# utilidong-ftdi-uart-mk-1_0.net
KiCad netlist of a schematic drawn in EAGLE
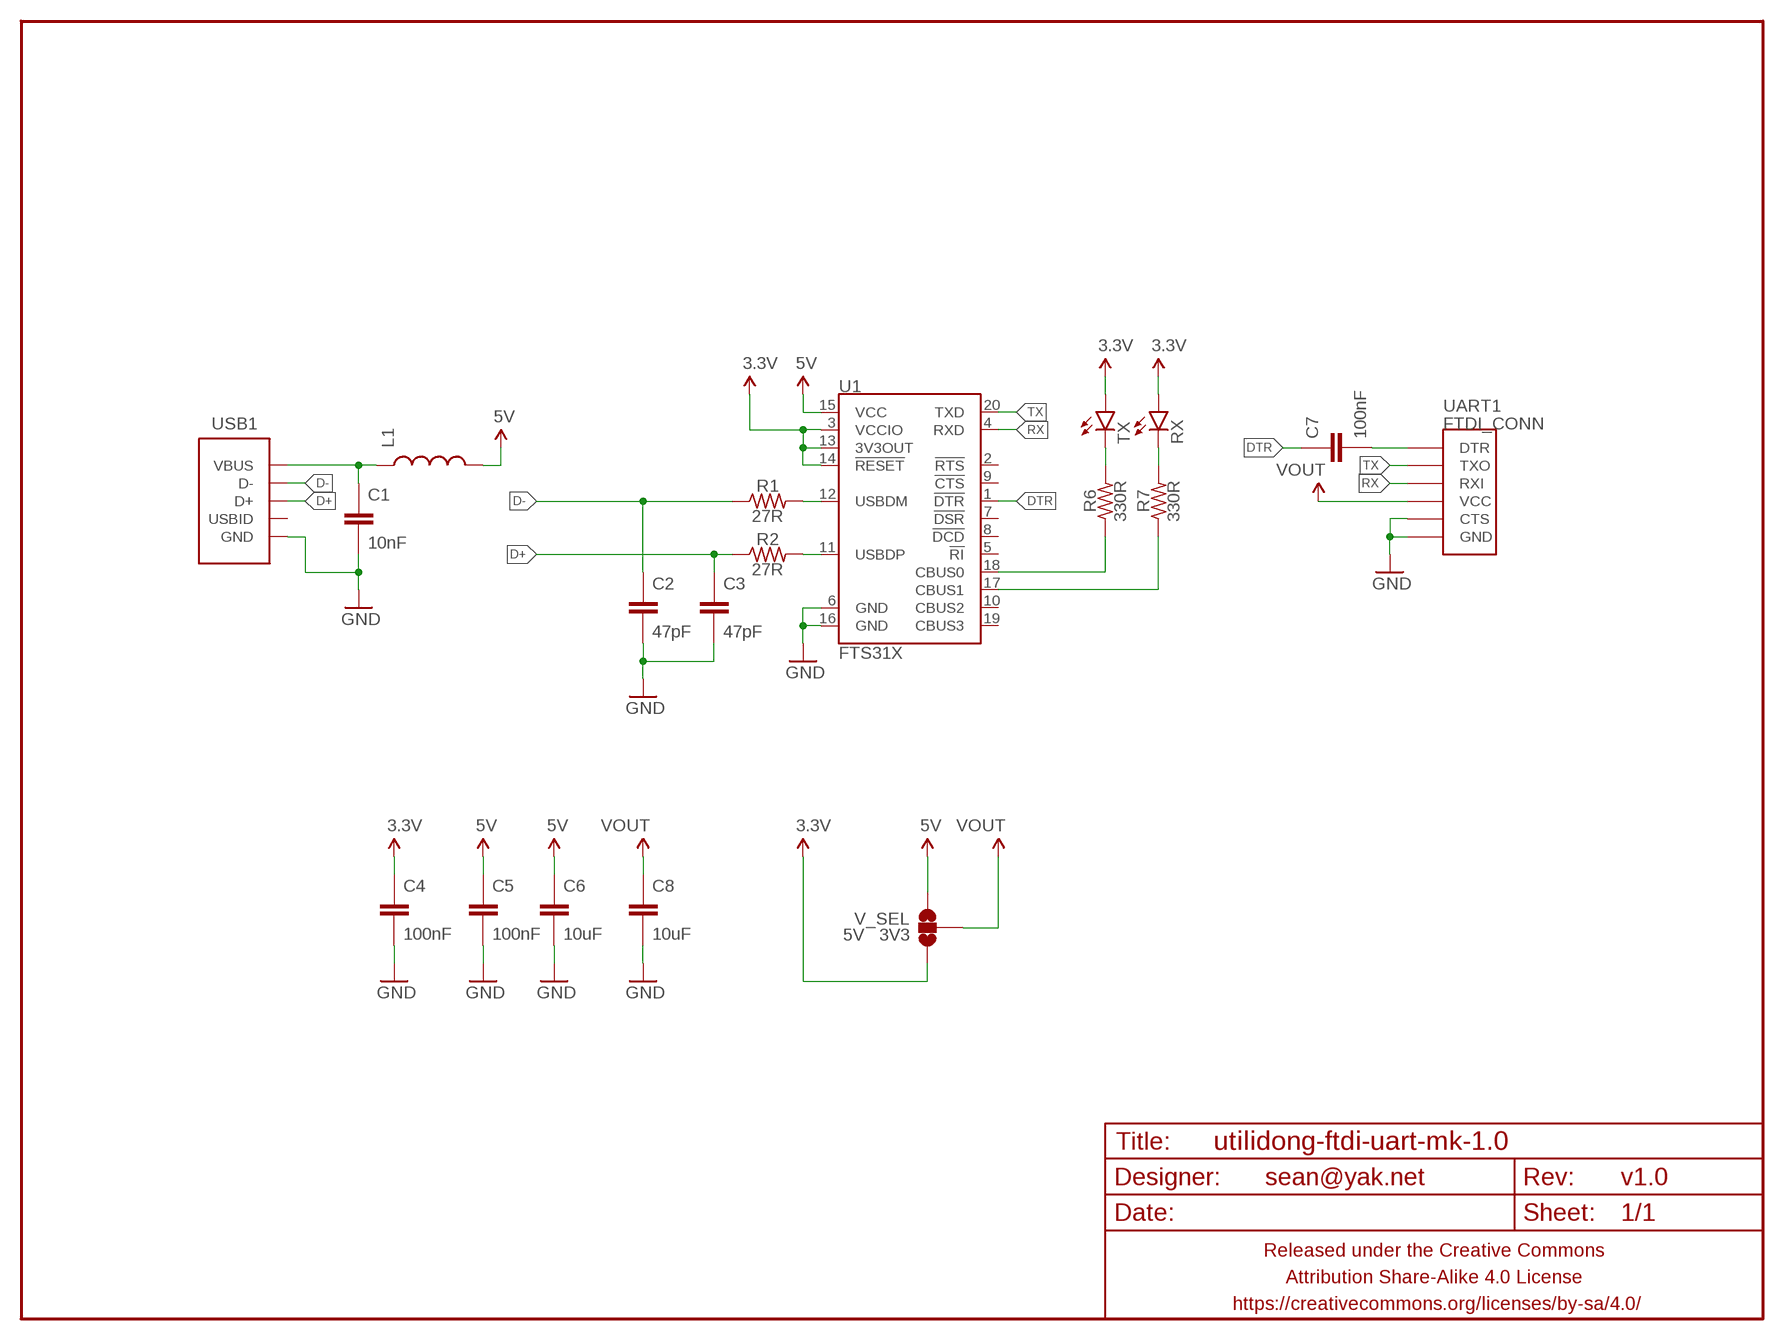
[diagram p0: schematic, sheet 1]

(export (version "E")
  (design (tool "Eeschema 10.0.6"))
  (components
    (comp (ref "C1")
      (value "10nF")
      (footprint "eagle-import:C0805")
      (libsource (lib "eagle-import") (part "CAPACITOR-CERAMICC0805"))
    )
    (comp (ref "C2")
      (value "47pF")
      (footprint "eagle-import:C0805")
      (libsource (lib "eagle-import") (part "CAPACITOR-CERAMICC0805"))
    )
    (comp (ref "C3")
      (value "47pF")
      (footprint "eagle-import:C0805")
      (libsource (lib "eagle-import") (part "CAPACITOR-CERAMICC0805"))
    )
    (comp (ref "C4")
      (value "100nF")
      (footprint "eagle-import:C0805")
      (libsource (lib "eagle-import") (part "CAPACITOR-CERAMICC0805"))
    )
    (comp (ref "C5")
      (value "100nF")
      (footprint "eagle-import:C0805")
      (libsource (lib "eagle-import") (part "CAPACITOR-CERAMICC0805"))
    )
    (comp (ref "C6")
      (value "10uF")
      (footprint "eagle-import:C1206")
      (libsource (lib "eagle-import") (part "CAPACITOR-CERAMICC1206"))
    )
    (comp (ref "C7")
      (value "100nF")
      (footprint "eagle-import:C0805")
      (libsource (lib "eagle-import") (part "CAPACITOR-CERAMICC0805"))
    )
    (comp (ref "C8")
      (value "10uF")
      (footprint "eagle-import:C1206")
      (libsource (lib "eagle-import") (part "CAPACITOR-CERAMICC1206"))
    )
    (comp (ref "FRAME1")
      (value "FRAME-LETTERNO_PACKAGE")
      (footprint "eagle-import:DUMMY")
      (fields (field (name "DESIGNER") "sean@yak.net") (field (name "VERSION") "v1.0"))
      (libsource (lib "eagle-import") (part "FRAME-LETTERNO_PACKAGE"))
    )
    (comp (ref "L1")
      (value "INDUCTORL0805")
      (footprint "eagle-import:L0805")
      (libsource (lib "eagle-import") (part "INDUCTORL0805"))
    )
    (comp (ref "R1")
      (value "27R")
      (footprint "eagle-import:R0805")
      (libsource (lib "eagle-import") (part "RESISTORR0805"))
    )
    (comp (ref "R2")
      (value "27R")
      (footprint "eagle-import:R0805")
      (libsource (lib "eagle-import") (part "RESISTORR0805"))
    )
    (comp (ref "R6")
      (value "330R")
      (footprint "eagle-import:R0805")
      (libsource (lib "eagle-import") (part "RESISTORR0805"))
    )
    (comp (ref "R7")
      (value "330R")
      (footprint "eagle-import:R0805")
      (libsource (lib "eagle-import") (part "RESISTORR0805"))
    )
    (comp (ref "RX")
      (value "LED1206")
      (footprint "eagle-import:LED-1206")
      (libsource (lib "eagle-import") (part "LED1206"))
    )
    (comp (ref "TX")
      (value "LED1206")
      (footprint "eagle-import:LED-1206")
      (libsource (lib "eagle-import") (part "LED1206"))
    )
    (comp (ref "U1")
      (value "FTS31X")
      (footprint "eagle-import:SSOP20_L")
      (libsource (lib "eagle-import") (part "FT231XS"))
    )
    (comp (ref "UART1")
      (value "FTDI_CONN")
      (footprint "eagle-import:FTDI_CONN")
      (libsource (lib "eagle-import") (part "FTDI_CONN"))
    )
    (comp (ref "USB1")
      (value "USB-ABCOMBO")
      (footprint "eagle-import:USB-MICRO-B-FCI-CUTOUT")
      (libsource (lib "eagle-import") (part "USB-ABCOMBO"))
    )
    (comp (ref "V_SEL")
      (value "5V 3V3")
      (footprint "eagle-import:PAD-JUMPER-3-NO_YES_SILK_FULL_BOX")
      (libsource (lib "eagle-import") (part "JUMPER-PAD-3-NOFULL_BOX_SILK"))
    )
  )
  (nets
    (net (code "1") (name "3.3V") (class "Default")
      (node (ref "C4") (pin "1") (pinfunction "1_1") (pintype "passive"))
      (node (ref "RX") (pin "A") (pinfunction "A_A") (pintype "passive"))
      (node (ref "TX") (pin "A") (pinfunction "A_A") (pintype "passive"))
      (node (ref "U1") (pin "13") (pinfunction "3V3OUT_13") (pintype "bidirectional"))
      (node (ref "U1") (pin "14") (pinfunction "~{RESET}_14") (pintype "bidirectional"))
      (node (ref "U1") (pin "3") (pinfunction "VCCIO_3") (pintype "bidirectional"))
      (node (ref "V_SEL") (pin "3") (pinfunction "3_3") (pintype "passive"))
    )
    (net (code "2") (name "5V") (class "Default")
      (node (ref "C5") (pin "1") (pinfunction "1_1") (pintype "passive"))
      (node (ref "C6") (pin "1") (pinfunction "1_1") (pintype "passive"))
      (node (ref "L1") (pin "2") (pinfunction "2_2") (pintype "passive"))
      (node (ref "U1") (pin "15") (pinfunction "VCC_15") (pintype "bidirectional"))
      (node (ref "V_SEL") (pin "1") (pinfunction "1_1") (pintype "passive"))
    )
    (net (code "3") (name "D+") (class "Default")
      (node (ref "C3") (pin "1") (pinfunction "1_1") (pintype "passive"))
      (node (ref "R2") (pin "1") (pinfunction "1_1") (pintype "passive"))
      (node (ref "USB1") (pin "3") (pinfunction "D+_3") (pintype "bidirectional"))
    )
    (net (code "4") (name "D-") (class "Default")
      (node (ref "C2") (pin "1") (pinfunction "1_1") (pintype "passive"))
      (node (ref "R1") (pin "1") (pinfunction "1_1") (pintype "passive"))
      (node (ref "USB1") (pin "2") (pinfunction "D-_2") (pintype "bidirectional"))
    )
    (net (code "5") (name "DTR") (class "Default")
      (node (ref "C7") (pin "1") (pinfunction "1_1") (pintype "passive"))
      (node (ref "U1") (pin "1") (pinfunction "~{DTR}_1") (pintype "bidirectional"))
    )
    (net (code "6") (name "GND") (class "Default")
      (node (ref "C1") (pin "2") (pinfunction "2_2") (pintype "passive"))
      (node (ref "C2") (pin "2") (pinfunction "2_2") (pintype "passive"))
      (node (ref "C3") (pin "2") (pinfunction "2_2") (pintype "passive"))
      (node (ref "C4") (pin "2") (pinfunction "2_2") (pintype "passive"))
      (node (ref "C5") (pin "2") (pinfunction "2_2") (pintype "passive"))
      (node (ref "C6") (pin "2") (pinfunction "2_2") (pintype "passive"))
      (node (ref "C8") (pin "2") (pinfunction "2_2") (pintype "passive"))
      (node (ref "U1") (pin "16") (pinfunction "GND_16") (pintype "bidirectional"))
      (node (ref "U1") (pin "6") (pinfunction "GND_6") (pintype "bidirectional"))
      (node (ref "UART1") (pin "CTS") (pinfunction "CTS_CTS") (pintype "bidirectional"))
      (node (ref "UART1") (pin "GND") (pinfunction "GND_GND") (pintype "bidirectional"))
      (node (ref "USB1") (pin "5") (pinfunction "GND_5") (pintype "bidirectional"))
      (node (ref "USB1") (pin "P$1") (pinfunction "GND_P$1") (pintype "bidirectional"))
      (node (ref "USB1") (pin "P$2") (pinfunction "GND_P$2") (pintype "bidirectional"))
    )
    (net (code "7") (name "Net-(C7-Pad2)") (class "Default")
      (node (ref "C7") (pin "2") (pinfunction "2_2") (pintype "passive"))
      (node (ref "UART1") (pin "DTR") (pinfunction "DTR_DTR") (pintype "bidirectional"))
    )
    (net (code "8") (name "Net-(R6-Pad2)") (class "Default")
      (node (ref "R6") (pin "2") (pinfunction "2_2") (pintype "passive"))
      (node (ref "TX") (pin "C") (pinfunction "C_C") (pintype "passive"))
    )
    (net (code "9") (name "Net-(R7-Pad2)") (class "Default")
      (node (ref "R7") (pin "2") (pinfunction "2_2") (pintype "passive"))
      (node (ref "RX") (pin "C") (pinfunction "C_C") (pintype "passive"))
    )
    (net (code "10") (name "Net-(U1-CBUS0)") (class "Default")
      (node (ref "R6") (pin "1") (pinfunction "1_1") (pintype "passive"))
      (node (ref "U1") (pin "18") (pinfunction "CBUS0_18") (pintype "bidirectional"))
    )
    (net (code "11") (name "Net-(U1-CBUS1)") (class "Default")
      (node (ref "R7") (pin "1") (pinfunction "1_1") (pintype "passive"))
      (node (ref "U1") (pin "17") (pinfunction "CBUS1_17") (pintype "bidirectional"))
    )
    (net (code "12") (name "Net-(U1-USBDM)") (class "Default")
      (node (ref "R1") (pin "2") (pinfunction "2_2") (pintype "passive"))
      (node (ref "U1") (pin "12") (pinfunction "USBDM_12") (pintype "bidirectional"))
    )
    (net (code "13") (name "Net-(U1-USBDP)") (class "Default")
      (node (ref "R2") (pin "2") (pinfunction "2_2") (pintype "passive"))
      (node (ref "U1") (pin "11") (pinfunction "USBDP_11") (pintype "bidirectional"))
    )
    (net (code "14") (name "Net-(USB1-VBUS)") (class "Default")
      (node (ref "C1") (pin "1") (pinfunction "1_1") (pintype "passive"))
      (node (ref "L1") (pin "1") (pinfunction "1_1") (pintype "passive"))
      (node (ref "USB1") (pin "1") (pinfunction "VBUS_1") (pintype "bidirectional"))
    )
    (net (code "15") (name "RX") (class "Default")
      (node (ref "U1") (pin "4") (pinfunction "RXD_4") (pintype "bidirectional"))
      (node (ref "UART1") (pin "RXI") (pinfunction "RXI_RXI") (pintype "bidirectional"))
    )
    (net (code "16") (name "TX") (class "Default")
      (node (ref "U1") (pin "20") (pinfunction "TXD_20") (pintype "bidirectional"))
      (node (ref "UART1") (pin "TXO") (pinfunction "TXO_TXO") (pintype "bidirectional"))
    )
    (net (code "17") (name "VOUT") (class "Default")
      (node (ref "C8") (pin "1") (pinfunction "1_1") (pintype "passive"))
      (node (ref "UART1") (pin "VCC") (pinfunction "VCC_VCC") (pintype "bidirectional"))
      (node (ref "V_SEL") (pin "2") (pinfunction "2_2") (pintype "passive"))
    )
    (net (code "18") (name "unconnected-(U1-CBUS2-Pad10)") (class "Default")
      (node (ref "U1") (pin "10") (pinfunction "CBUS2_10") (pintype "bidirectional"))
    )
    (net (code "19") (name "unconnected-(U1-CBUS3-Pad19)") (class "Default")
      (node (ref "U1") (pin "19") (pinfunction "CBUS3_19") (pintype "bidirectional"))
    )
    (net (code "20") (name "unconnected-(U1-~{CTS}-Pad9)") (class "Default")
      (node (ref "U1") (pin "9") (pinfunction "~{CTS}_9") (pintype "bidirectional"))
    )
    (net (code "21") (name "unconnected-(U1-~{DCD}-Pad8)") (class "Default")
      (node (ref "U1") (pin "8") (pinfunction "~{DCD}_8") (pintype "bidirectional"))
    )
    (net (code "22") (name "unconnected-(U1-~{DSR}-Pad7)") (class "Default")
      (node (ref "U1") (pin "7") (pinfunction "~{DSR}_7") (pintype "bidirectional"))
    )
    (net (code "23") (name "unconnected-(U1-~{RI}-Pad5)") (class "Default")
      (node (ref "U1") (pin "5") (pinfunction "~{RI}_5") (pintype "bidirectional"))
    )
    (net (code "24") (name "unconnected-(U1-~{RTS}-Pad2)") (class "Default")
      (node (ref "U1") (pin "2") (pinfunction "~{RTS}_2") (pintype "bidirectional"))
    )
    (net (code "25") (name "unconnected-(USB1-USBID-Pad4)") (class "Default")
      (node (ref "USB1") (pin "4") (pinfunction "USBID_4") (pintype "bidirectional"))
    )
  )
)
